# USB_OTG_HS.net
KiCad netlist of a schematic drawn in Altium Designer
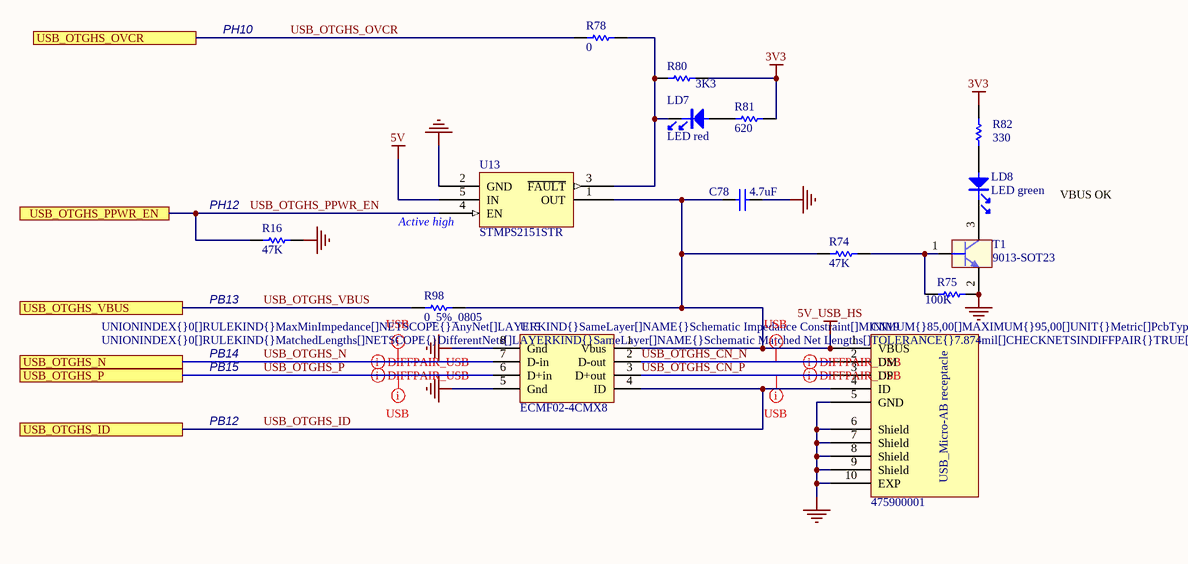
[diagram p0: USB_OTG_HS.SchDoc]

(export (version "E")
  (design (tool "Eeschema 10.0.6"))
  (components
    (comp (ref "C78")
      (value "4.7uF")
      (footprint "0603C")
      (description "Capacitor,4.7uF,16V, X5R,10%,0603,YAGEO")
      (libsource (lib "MCD_TOOLS") (part "Cap_4.7uF_X5R_10%_0603"))
    )
    (comp (ref "CN19")
      (value "475900001")
      (footprint "MOLEX_47590001")
      (description "USB-MICRO-AB, 47590-0001, SMT, MOLEX")
      (libsource (lib "MCD_TOOLS") (part "475900001"))
    )
    (comp (ref "LD7")
      (value "LED red")
      (footprint "0603D")
      (description "LED red 0603")
      (libsource (lib "MCD_TEMP_NPA") (part "LED_red"))
    )
    (comp (ref "LD8")
      (value "LED green")
      (footprint "0603D")
      (description "LED green 0603")
      (libsource (lib "MCD_TEMP_NPA") (part "LED_green"))
    )
    (comp (ref "R16")
      (value "47K")
      (footprint "0402R")
      (description "Resistor,47K,0402,1%,YAGEO")
      (fields (field (name "Comment") "47K_1%_0402"))
      (libsource (lib "MCD_TOOLS_RESISTOR") (part "Res_47K_1%_0402"))
    )
    (comp (ref "R74")
      (value "47K")
      (footprint "0402R")
      (description "Resistor,47K,0402,1%,YAGEO")
      (fields (field (name "Comment") "47K_1%_0402"))
      (libsource (lib "MCD_TOOLS_RESISTOR") (part "Res_47K_1%_0402"))
    )
    (comp (ref "R75")
      (value "100K")
      (footprint "0402R")
      (description "Resistor,100K,0402,1%,YAGEO")
      (fields (field (name "Comment") "100K_1%_0402"))
      (libsource (lib "MCD_TOOLS_RESISTOR") (part "Res_100K_1%_0402"))
    )
    (comp (ref "R78")
      (value "0")
      (footprint "0402R")
      (description "Resistor,0,0402,5%,YAGEO")
      (libsource (lib "MCD_TOOLS") (part "Res_0_5%_0402"))
    )
    (comp (ref "R80")
      (value "3K3")
      (footprint "0402R")
      (description "Resistor,3K3,0402,1%,YAGEO")
      (libsource (lib "MCD_TOOLS") (part "Res_3K3_1%_0402"))
    )
    (comp (ref "R81")
      (value "620")
      (footprint "0603R")
      (description "Resistor,620,0603,1%,VISHAY")
      (fields (field (name "Comment") "620_1%_0603"))
      (libsource (lib "MCD_TOOLS_RESISTOR") (part "Res_620_1%_0603"))
    )
    (comp (ref "R82")
      (value "330")
      (footprint "0603R")
      (description "Resistor,330,0603,1%,YAGEO")
      (fields (field (name "Comment") "330_1%_0603"))
      (libsource (lib "MCD_TOOLS_RESISTOR") (part "Res_330_1%_0603"))
    )
    (comp (ref "R98")
      (value "0_5%_0805")
      (footprint "0805R")
      (description "Resistor,0,0805,5%,YAGEO")
      (libsource (lib "MCD_TOOLS_RESISTOR") (part "Res_0_5%_0805"))
    )
    (comp (ref "T1")
      (value "9013-SOT23")
      (footprint "SOT-23")
      (description "NPN Bipolar Transistor")
      (libsource (lib "MCD_TOOLS_MISCELLANEOUS") (part "9013-SOT23"))
    )
    (comp (ref "U13")
      (value "STMPS2151STR")
      (footprint "SOT23-5")
      (description "Enhanced single channel power switches")
      (libsource (lib "MCD_TEMP_NPA") (part "STMPS2151STR"))
    )
    (comp (ref "U15")
      (value "ECMF02-4CMX8")
      (footprint "QFN8_0R5_2R5X1R2")
      (description "Common mode filter with ESD protection for USB 2.0 interface")
      (libsource (lib "MCD_TEMP_NPA") (part "ECMF02-4CMX8"))
    )
  )
  (nets
    (net (code "1") (name "/USB_OTGHS_CN_N") (class "Default")
      (node (ref "CN19") (pin "2") (pinfunction "DM_2") (pintype "passive"))
      (node (ref "U15") (pin "2") (pinfunction "D-out_2") (pintype "passive"))
    )
    (net (code "2") (name "/USB_OTGHS_CN_P") (class "Default")
      (node (ref "CN19") (pin "3") (pinfunction "DP_3") (pintype "passive"))
      (node (ref "U15") (pin "3") (pinfunction "D+out_3") (pintype "passive"))
    )
    (net (code "3") (name "/USB_OTGHS_ID") (class "Default")
      (node (ref "CN19") (pin "4") (pinfunction "ID_4") (pintype "passive"))
      (node (ref "U15") (pin "4") (pinfunction "ID_4") (pintype "passive"))
    )
    (net (code "4") (name "/USB_OTGHS_N") (class "Default")
      (node (ref "U15") (pin "7") (pinfunction "D-in_7") (pintype "passive"))
    )
    (net (code "5") (name "/USB_OTGHS_OVCR") (class "Default")
      (node (ref "R78") (pin "2") (pinfunction "2_2") (pintype "passive"))
    )
    (net (code "6") (name "/USB_OTGHS_P") (class "Default")
      (node (ref "U15") (pin "6") (pinfunction "D+in_6") (pintype "passive"))
    )
    (net (code "7") (name "/USB_OTGHS_PPWR_EN") (class "Default")
      (node (ref "R16") (pin "2") (pinfunction "2_2") (pintype "passive"))
      (node (ref "U13") (pin "4") (pinfunction "EN_4") (pintype "input"))
    )
    (net (code "8") (name "/USB_OTGHS_VBUS") (class "Default")
      (node (ref "R98") (pin "1") (pinfunction "1_1") (pintype "passive"))
    )
    (net (code "9") (name "3V3") (class "Default")
      (node (ref "R80") (pin "1") (pinfunction "1_1") (pintype "passive"))
      (node (ref "R81") (pin "1") (pinfunction "1_1") (pintype "passive"))
      (node (ref "R82") (pin "2") (pinfunction "2_2") (pintype "passive"))
    )
    (net (code "10") (name "5V") (class "Default")
      (node (ref "U13") (pin "5") (pinfunction "IN_5") (pintype "passive"))
    )
    (net (code "11") (name "5V_USB_HS") (class "Default")
      (node (ref "C78") (pin "1") (pinfunction "1_1") (pintype "passive"))
      (node (ref "CN19") (pin "1") (pinfunction "VBUS_1") (pintype "passive"))
      (node (ref "R74") (pin "2") (pinfunction "2_2") (pintype "passive"))
      (node (ref "R98") (pin "2") (pinfunction "2_2") (pintype "passive"))
      (node (ref "U13") (pin "1") (pinfunction "OUT_1") (pintype "passive"))
      (node (ref "U15") (pin "1") (pinfunction "Vbus_1") (pintype "passive"))
    )
    (net (code "12") (name "GND") (class "Default")
      (node (ref "C78") (pin "2") (pinfunction "2_2") (pintype "passive"))
      (node (ref "CN19") (pin "10") (pinfunction "EXP_10") (pintype "passive"))
      (node (ref "CN19") (pin "5") (pinfunction "GND_5") (pintype "passive"))
      (node (ref "CN19") (pin "6") (pinfunction "Shield_6") (pintype "passive"))
      (node (ref "CN19") (pin "7") (pinfunction "Shield_7") (pintype "passive"))
      (node (ref "CN19") (pin "8") (pinfunction "Shield_8") (pintype "passive"))
      (node (ref "CN19") (pin "9") (pinfunction "Shield_9") (pintype "passive"))
      (node (ref "R16") (pin "1") (pinfunction "1_1") (pintype "passive"))
      (node (ref "R75") (pin "2") (pinfunction "2_2") (pintype "passive"))
      (node (ref "T1") (pin "2") (pinfunction "E_2") (pintype "passive"))
      (node (ref "U13") (pin "2") (pinfunction "GND_2") (pintype "passive"))
      (node (ref "U15") (pin "5") (pinfunction "Gnd_5") (pintype "passive"))
      (node (ref "U15") (pin "8") (pinfunction "Gnd_8") (pintype "passive"))
    )
    (net (code "13") (name "Net-(LD7-Pad1)") (class "Default")
      (node (ref "LD7") (pin "1") (pintype "passive"))
      (node (ref "R81") (pin "2") (pinfunction "2_2") (pintype "passive"))
    )
    (net (code "14") (name "Net-(LD8-Pad1)") (class "Default")
      (node (ref "LD8") (pin "1") (pintype "passive"))
      (node (ref "R82") (pin "1") (pinfunction "1_1") (pintype "passive"))
    )
    (net (code "15") (name "Net-(T1-B)") (class "Default")
      (node (ref "R74") (pin "1") (pinfunction "1_1") (pintype "passive"))
      (node (ref "R75") (pin "1") (pinfunction "1_1") (pintype "passive"))
      (node (ref "T1") (pin "1") (pinfunction "B_1") (pintype "passive"))
    )
    (net (code "16") (name "Net-(T1-C)") (class "Default")
      (node (ref "LD8") (pin "2") (pintype "passive"))
      (node (ref "T1") (pin "3") (pinfunction "C_3") (pintype "passive"))
    )
    (net (code "17") (name "Net-(U13-~{FAULT})") (class "Default")
      (node (ref "LD7") (pin "2") (pintype "passive"))
      (node (ref "R78") (pin "1") (pinfunction "1_1") (pintype "passive"))
      (node (ref "R80") (pin "2") (pinfunction "2_2") (pintype "passive"))
      (node (ref "U13") (pin "3") (pinfunction "~{FAULT}_3") (pintype "output"))
    )
  )
)
